# Esquematico.net
KiCad netlist of a schematic drawn in Altium Designer
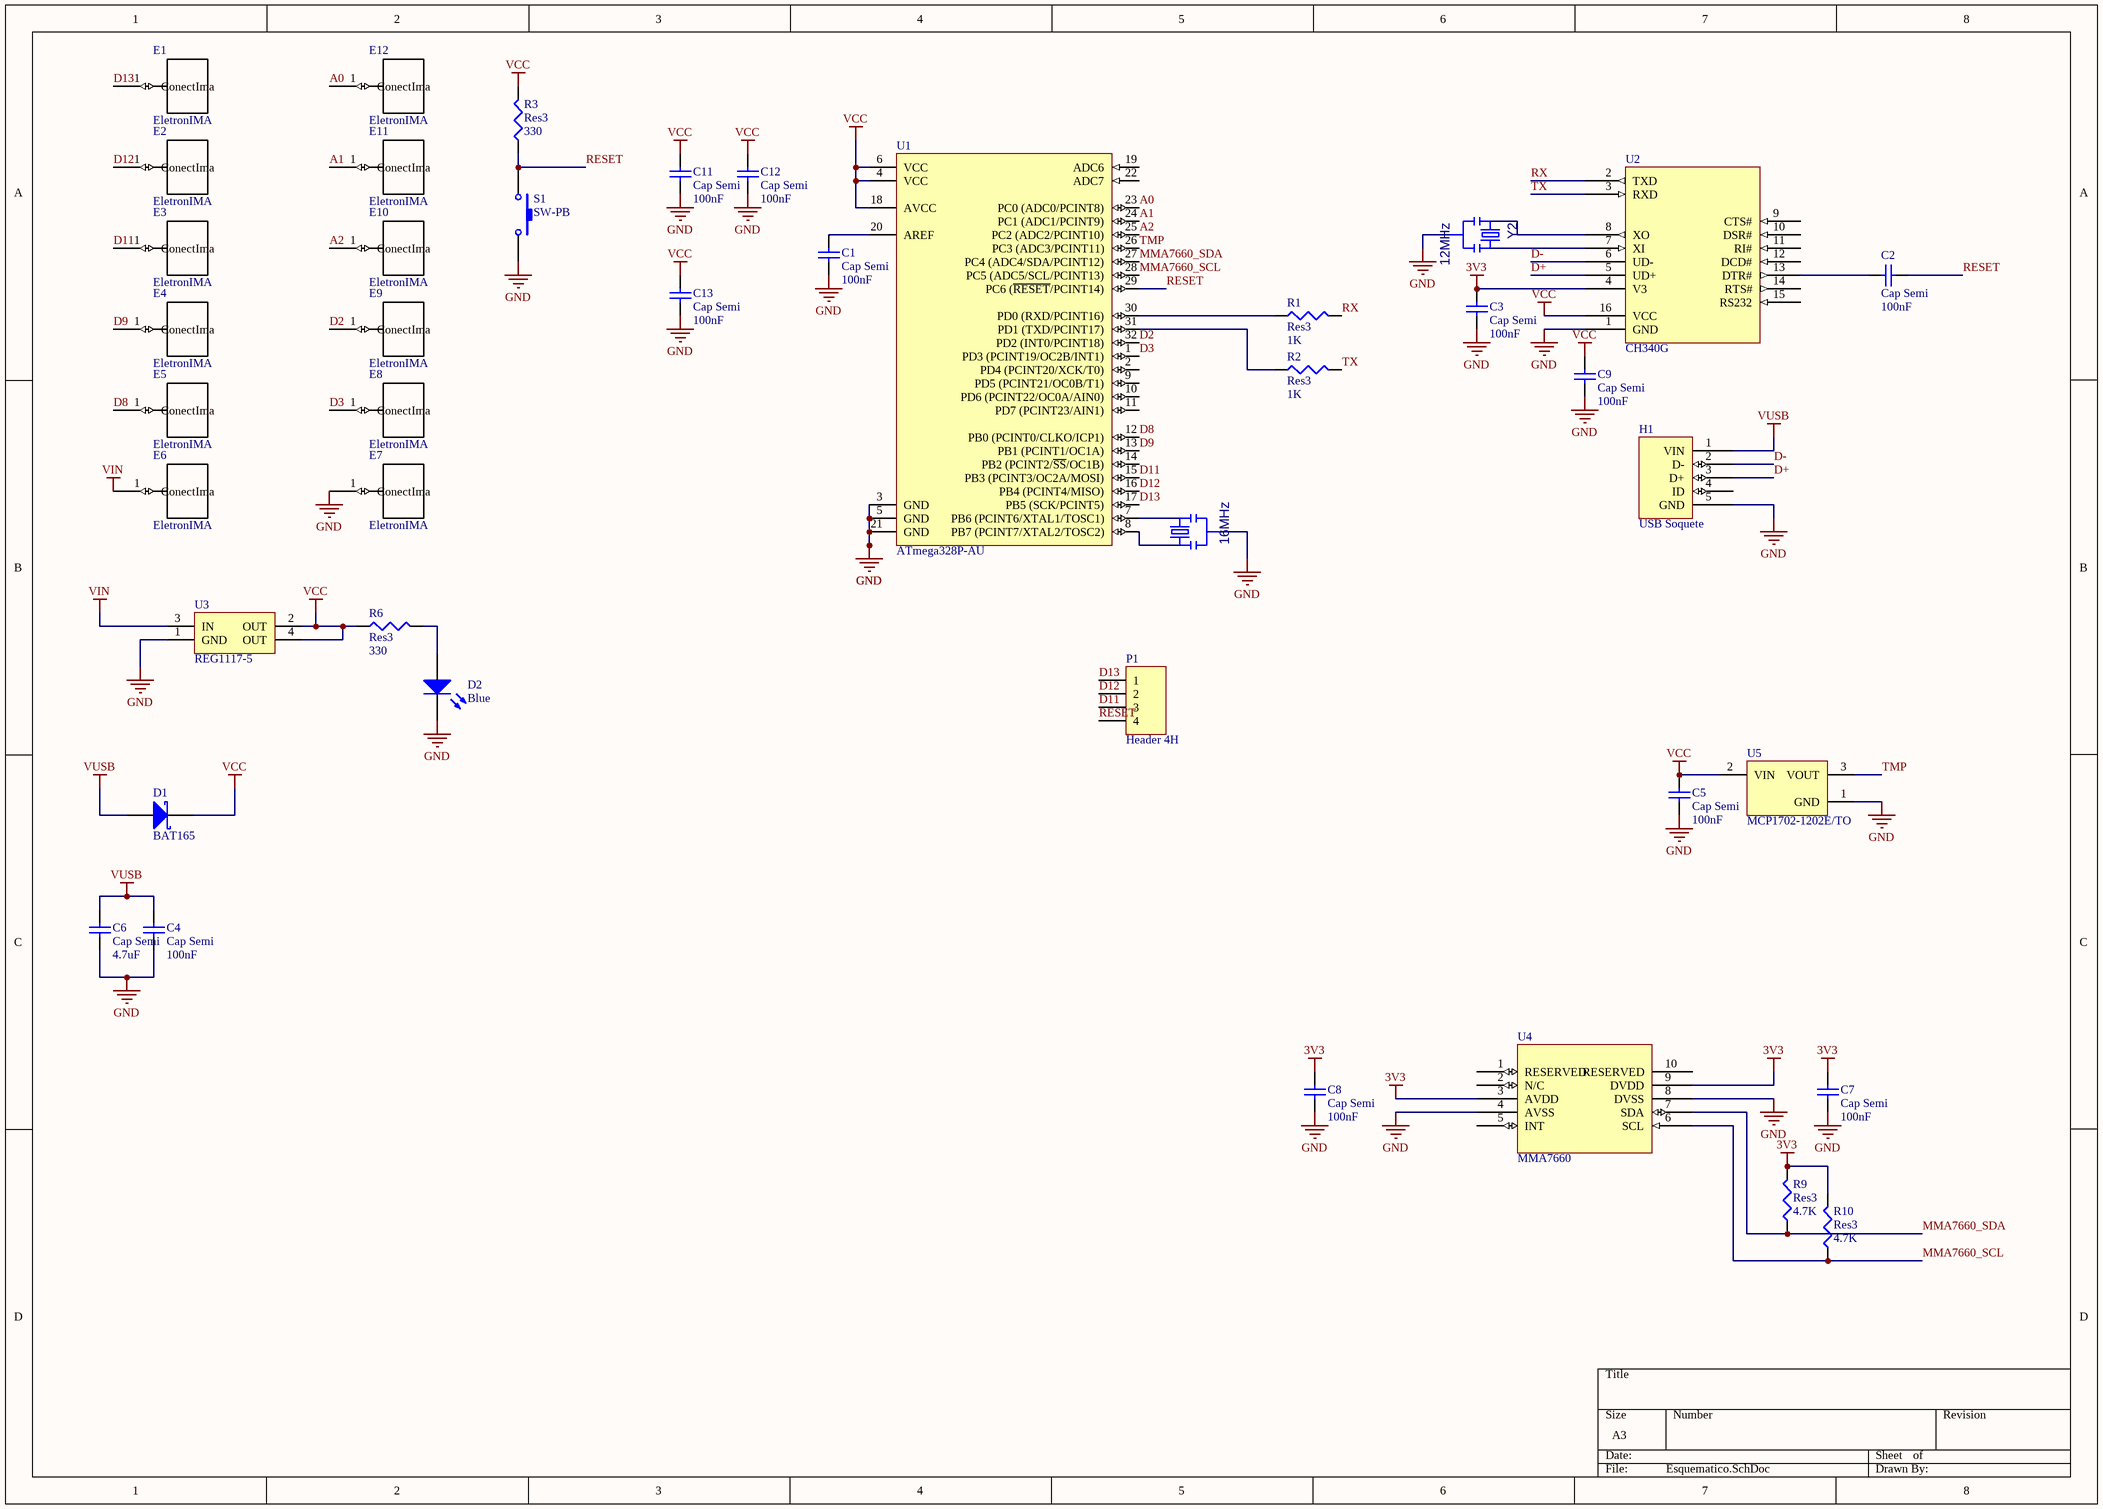
[diagram p0: Esquematico.SchDoc]

(export (version "E")
  (design (tool "Eeschema 10.0.6"))
  (components
    (comp (ref "C1")
      (value "Cap Semi")
      (footprint "0402")
      (description "Capacitor (Semiconductor SIM Model)")
      (fields (field (name "ALTIUM_VALUE") "100nF") (field (name "PUBLISHER") "Altium Limited"))
      (libsource (lib "Miscellaneous Devices") (part "Cap Semi"))
    )
    (comp (ref "C2")
      (value "Cap Semi")
      (footprint "0402")
      (description "Capacitor (Semiconductor SIM Model)")
      (fields (field (name "ALTIUM_VALUE") "100nF") (field (name "PUBLISHER") "Altium Limited"))
      (libsource (lib "Miscellaneous Devices") (part "Cap Semi"))
    )
    (comp (ref "C3")
      (value "Cap Semi")
      (footprint "0402")
      (description "Capacitor (Semiconductor SIM Model)")
      (fields (field (name "ALTIUM_VALUE") "100nF") (field (name "PUBLISHER") "Altium Limited"))
      (libsource (lib "Miscellaneous Devices") (part "Cap Semi"))
    )
    (comp (ref "C4")
      (value "Cap Semi")
      (footprint "0402")
      (description "Capacitor (Semiconductor SIM Model)")
      (fields (field (name "ALTIUM_VALUE") "100nF") (field (name "PUBLISHER") "Altium Limited"))
      (libsource (lib "Miscellaneous Devices") (part "Cap Semi"))
    )
    (comp (ref "C5")
      (value "Cap Semi")
      (footprint "0402")
      (description "Capacitor (Semiconductor SIM Model)")
      (fields (field (name "ALTIUM_VALUE") "100nF") (field (name "PUBLISHER") "Altium Limited"))
      (libsource (lib "Miscellaneous Devices") (part "Cap Semi"))
    )
    (comp (ref "C6")
      (value "Cap Semi")
      (footprint "0402")
      (description "Capacitor (Semiconductor SIM Model)")
      (fields (field (name "ALTIUM_VALUE") "4.7uF") (field (name "PUBLISHER") "Altium Limited"))
      (libsource (lib "Miscellaneous Devices") (part "Cap Semi"))
    )
    (comp (ref "C7")
      (value "Cap Semi")
      (footprint "0402")
      (description "Capacitor (Semiconductor SIM Model)")
      (fields (field (name "ALTIUM_VALUE") "100nF") (field (name "PUBLISHER") "Altium Limited"))
      (libsource (lib "Miscellaneous Devices") (part "Cap Semi"))
    )
    (comp (ref "C8")
      (value "Cap Semi")
      (footprint "0402")
      (description "Capacitor (Semiconductor SIM Model)")
      (fields (field (name "ALTIUM_VALUE") "100nF") (field (name "PUBLISHER") "Altium Limited"))
      (libsource (lib "Miscellaneous Devices") (part "Cap Semi"))
    )
    (comp (ref "C9")
      (value "Cap Semi")
      (footprint "0402")
      (description "Capacitor (Semiconductor SIM Model)")
      (fields (field (name "ALTIUM_VALUE") "100nF") (field (name "PUBLISHER") "Altium Limited"))
      (libsource (lib "Miscellaneous Devices") (part "Cap Semi"))
    )
    (comp (ref "C11")
      (value "Cap Semi")
      (footprint "0402")
      (description "Capacitor (Semiconductor SIM Model)")
      (fields (field (name "ALTIUM_VALUE") "100nF") (field (name "PUBLISHER") "Altium Limited"))
      (libsource (lib "Miscellaneous Devices") (part "Cap Semi"))
    )
    (comp (ref "C12")
      (value "Cap Semi")
      (footprint "0402")
      (description "Capacitor (Semiconductor SIM Model)")
      (fields (field (name "ALTIUM_VALUE") "100nF") (field (name "PUBLISHER") "Altium Limited"))
      (libsource (lib "Miscellaneous Devices") (part "Cap Semi"))
    )
    (comp (ref "C13")
      (value "Cap Semi")
      (footprint "0402")
      (description "Capacitor (Semiconductor SIM Model)")
      (fields (field (name "ALTIUM_VALUE") "100nF") (field (name "PUBLISHER") "Altium Limited"))
      (libsource (lib "Miscellaneous Devices") (part "Cap Semi"))
    )
    (comp (ref "D1")
      (value "BAT165")
      (footprint "SOD-323")
      (description "Silicon AF Schottky Rectifier Diode")
      (fields (field (name "PUBLISHER") "Altium Limited"))
      (libsource (lib "Infineon Discrete Diode") (part "BAT165"))
    )
    (comp (ref "D2")
      (value "Blue")
      (footprint "1.6X0.8X0.6")
      (description "Top Mount Low Profile Chip LED, Blue")
      (fields (field (name "PUBLISHER") "Altium Limited"))
      (libsource (lib "Agilent Optoelectronic LED") (part "HSMR-C191"))
    )
    (comp (ref "E1")
      (value "EletronIMA")
      (footprint "TermIma")
      (libsource (lib "Components") (part "EletronIMA"))
    )
    (comp (ref "E2")
      (value "EletronIMA")
      (footprint "TermIma")
      (libsource (lib "Components") (part "EletronIMA"))
    )
    (comp (ref "E3")
      (value "EletronIMA")
      (footprint "TermIma")
      (libsource (lib "Components") (part "EletronIMA"))
    )
    (comp (ref "E4")
      (value "EletronIMA")
      (footprint "TermIma")
      (libsource (lib "Components") (part "EletronIMA"))
    )
    (comp (ref "E5")
      (value "EletronIMA")
      (footprint "TermIma")
      (libsource (lib "Components") (part "EletronIMA"))
    )
    (comp (ref "E6")
      (value "EletronIMA")
      (footprint "TermIma")
      (libsource (lib "Components") (part "EletronIMA"))
    )
    (comp (ref "E7")
      (value "EletronIMA")
      (footprint "TermIma")
      (libsource (lib "Components") (part "EletronIMA"))
    )
    (comp (ref "E8")
      (value "EletronIMA")
      (footprint "TermIma")
      (libsource (lib "Components") (part "EletronIMA"))
    )
    (comp (ref "E9")
      (value "EletronIMA")
      (footprint "TermIma")
      (libsource (lib "Components") (part "EletronIMA"))
    )
    (comp (ref "E10")
      (value "EletronIMA")
      (footprint "TermIma")
      (libsource (lib "Components") (part "EletronIMA"))
    )
    (comp (ref "E11")
      (value "EletronIMA")
      (footprint "TermIma")
      (libsource (lib "Components") (part "EletronIMA"))
    )
    (comp (ref "E12")
      (value "EletronIMA")
      (footprint "TermIma")
      (libsource (lib "Components") (part "EletronIMA"))
    )
    (comp (ref "H1")
      (value "USB Soquete")
      (footprint "ZX62RD-AB-5P8")
      (libsource (lib "Components") (part "USB Soquete"))
    )
    (comp (ref "P1")
      (value "Header 4H")
      (footprint "HDR1X4H")
      (description "Header, 4-Pin, Right Angle")
      (fields (field (name "PUBLISHER") "Altium Limited"))
      (libsource (lib "Miscellaneous Connectors") (part "Header 4H"))
    )
    (comp (ref "R1")
      (value "Res3")
      (footprint "J1-0603")
      (description "Resistor")
      (fields (field (name "ALTIUM_VALUE") "1K") (field (name "PUBLISHER") "Altium Limited"))
      (libsource (lib "Miscellaneous Devices") (part "Res3"))
    )
    (comp (ref "R2")
      (value "Res3")
      (footprint "J1-0603")
      (description "Resistor")
      (fields (field (name "ALTIUM_VALUE") "1K") (field (name "PUBLISHER") "Altium Limited"))
      (libsource (lib "Miscellaneous Devices") (part "Res3"))
    )
    (comp (ref "R3")
      (value "Res3")
      (footprint "J1-0603")
      (description "Resistor")
      (fields (field (name "ALTIUM_VALUE") "330") (field (name "PUBLISHER") "Altium Limited"))
      (libsource (lib "Miscellaneous Devices") (part "Res3"))
    )
    (comp (ref "R6")
      (value "Res3")
      (footprint "J1-0603")
      (description "Resistor")
      (fields (field (name "ALTIUM_VALUE") "330") (field (name "PUBLISHER") "Altium Limited"))
      (libsource (lib "Miscellaneous Devices") (part "Res3"))
    )
    (comp (ref "R9")
      (value "Res3")
      (footprint "J1-0603")
      (description "Resistor")
      (fields (field (name "ALTIUM_VALUE") "4.7K") (field (name "PUBLISHER") "Altium Limited"))
      (libsource (lib "Miscellaneous Devices") (part "Res3"))
    )
    (comp (ref "R10")
      (value "Res3")
      (footprint "J1-0603")
      (description "Resistor")
      (fields (field (name "ALTIUM_VALUE") "4.7K") (field (name "PUBLISHER") "Altium Limited"))
      (libsource (lib "Miscellaneous Devices") (part "Res3"))
    )
    (comp (ref "S1")
      (value "SW-PB")
      (footprint "SPST")
      (description "Switch")
      (fields (field (name "PUBLISHER") "Altium Limited"))
      (libsource (lib "Miscellaneous Devices") (part "SW-PB"))
    )
    (comp (ref "U1")
      (value "ATmega328P-AU")
      (footprint "32A_N")
      (fields (field (name "PUBLISHER") "Altium Limited"))
      (libsource (lib "Atmel Microcontroller 8-Bit megaAVR") (part "ATmega328P-AU"))
    )
    (comp (ref "U2")
      (value "CH340G")
      (footprint "SSOP20")
      (description "USB to UART interface")
      (libsource (lib "Components") (part "CH340G"))
    )
    (comp (ref "U3")
      (value "REG1117-5")
      (footprint "SOT-223-DB3_M")
      (description "800mA and 1A Low Dropout Positive Regulator 2.85V, 3.3V, 5V, and Adjustable")
      (fields (field (name "PUBLISHER") "Altium Limited"))
      (libsource (lib "BB Power Mgt Voltage Regulator") (part "REG1117-5"))
    )
    (comp (ref "U4")
      (value "MMA7660")
      (footprint "Microchip Linear Devices:DFN-MF10")
      (description "Digital 3-Axis-Accelerometers Sensor;±16g")
      (libsource (lib "Components") (part "MMA7660"))
    )
    (comp (ref "U5")
      (value "MCP1702-1202E/TO")
      (footprint "TO-92-TO3")
      (description "250 mA Low Quiescent Current LDO Regulator, 3-Pin TO-92, Extended TemperatureBAG")
      (fields (field (name "PUBLISHER") "Altium Limited"))
      (libsource (lib "Microchip Power Mgt Line Regulator") (part "MCP1702-1202E/TO"))
    )
    (comp (ref "Y1")
      (value "16MHz")
      (footprint "X3-SMD-3.6X1.3X0.8MM")
      (description "Ceramic Resonator 16MHz ??0.5% (Tol) ??0.3% (Stability) 15pF 40Ohm 3-Pin CSMD T/R")
      (fields (field (name "MP") "CSTCE16M0V53-R0") (field (name "MF") "Murata"))
      (libsource (lib "SMD-RESONATOR-16MHZ-15PF-0.5_-40R_3P-3.2X1.3MM_") (part "SMD-RESONATOR-16MHZ-15PF-0.5%-40R(3P-3.2X1.3MM)"))
    )
    (comp (ref "Y2")
      (value "12MHz")
      (footprint "X3-SMD-3.6X1.3X0.8MM")
      (description "Ceramic Resonator 16MHz ??0.5% (Tol) ??0.3% (Stability) 15pF 40Ohm 3-Pin CSMD T/R")
      (fields (field (name "MP") "CSTCE16M0V53-R0") (field (name "MF") "Murata"))
      (libsource (lib "SMD-RESONATOR-16MHZ-15PF-0.5_-40R_3P-3.2X1.3MM_") (part "SMD-RESONATOR-16MHZ-15PF-0.5%-40R(3P-3.2X1.3MM)"))
    )
  )
  (nets
    (net (code "1") (name "/A0") (class "Default")
      (node (ref "E12") (pin "1") (pinfunction "ConectIma_1") (pintype "bidirectional"))
      (node (ref "U1") (pin "23") (pinfunction "PC0_(ADC0/PCINT8)_23") (pintype "bidirectional"))
    )
    (net (code "2") (name "/A1") (class "Default")
      (node (ref "E11") (pin "1") (pinfunction "ConectIma_1") (pintype "bidirectional"))
      (node (ref "U1") (pin "24") (pinfunction "PC1_(ADC1/PCINT9)_24") (pintype "bidirectional"))
    )
    (net (code "3") (name "/A2") (class "Default")
      (node (ref "E10") (pin "1") (pinfunction "ConectIma_1") (pintype "bidirectional"))
      (node (ref "U1") (pin "25") (pinfunction "PC2_(ADC2/PCINT10)_25") (pintype "bidirectional"))
    )
    (net (code "4") (name "/D+") (class "Default")
      (node (ref "H1") (pin "3") (pinfunction "D+_3") (pintype "bidirectional"))
      (node (ref "U2") (pin "5") (pinfunction "UD+_5") (pintype "open_collector"))
    )
    (net (code "5") (name "/D-") (class "Default")
      (node (ref "H1") (pin "2") (pinfunction "D-_2") (pintype "bidirectional"))
      (node (ref "U2") (pin "6") (pinfunction "UD-_6") (pintype "open_collector"))
    )
    (net (code "6") (name "/D2") (class "Default")
      (node (ref "E9") (pin "1") (pinfunction "ConectIma_1") (pintype "bidirectional"))
      (node (ref "U1") (pin "32") (pinfunction "PD2_(INT0/PCINT18)_32") (pintype "bidirectional"))
    )
    (net (code "7") (name "/D3") (class "Default")
      (node (ref "E8") (pin "1") (pinfunction "ConectIma_1") (pintype "bidirectional"))
      (node (ref "U1") (pin "1") (pinfunction "PD3_(PCINT19/OC2B/INT1)_1") (pintype "bidirectional"))
    )
    (net (code "8") (name "/D8") (class "Default")
      (node (ref "E5") (pin "1") (pinfunction "ConectIma_1") (pintype "bidirectional"))
      (node (ref "U1") (pin "12") (pinfunction "PB0_(PCINT0/CLKO/ICP1)_12") (pintype "bidirectional"))
    )
    (net (code "9") (name "/D9") (class "Default")
      (node (ref "E4") (pin "1") (pinfunction "ConectIma_1") (pintype "bidirectional"))
      (node (ref "U1") (pin "13") (pinfunction "PB1_(PCINT1/OC1A)_13") (pintype "bidirectional"))
    )
    (net (code "10") (name "/D11") (class "Default")
      (node (ref "E3") (pin "1") (pinfunction "ConectIma_1") (pintype "bidirectional"))
      (node (ref "P1") (pin "3") (pinfunction "3_3") (pintype "passive"))
      (node (ref "U1") (pin "15") (pinfunction "PB3_(PCINT3/OC2A/MOSI)_15") (pintype "bidirectional"))
    )
    (net (code "11") (name "/D12") (class "Default")
      (node (ref "E2") (pin "1") (pinfunction "ConectIma_1") (pintype "bidirectional"))
      (node (ref "P1") (pin "2") (pinfunction "2_2") (pintype "passive"))
      (node (ref "U1") (pin "16") (pinfunction "PB4_(PCINT4/MISO)_16") (pintype "bidirectional"))
    )
    (net (code "12") (name "/D13") (class "Default")
      (node (ref "E1") (pin "1") (pinfunction "ConectIma_1") (pintype "bidirectional"))
      (node (ref "P1") (pin "1") (pinfunction "1_1") (pintype "passive"))
      (node (ref "U1") (pin "17") (pinfunction "PB5_(SCK/PCINT5)_17") (pintype "bidirectional"))
    )
    (net (code "13") (name "/MMA7660_SCL") (class "Default")
      (node (ref "R10") (pin "1") (pinfunction "1_1") (pintype "passive"))
      (node (ref "U1") (pin "28") (pinfunction "PC5_(ADC5/SCL/PCINT13)_28") (pintype "bidirectional"))
      (node (ref "U4") (pin "6") (pinfunction "SCL_6") (pintype "input"))
    )
    (net (code "14") (name "/MMA7660_SDA") (class "Default")
      (node (ref "R9") (pin "1") (pinfunction "1_1") (pintype "passive"))
      (node (ref "U1") (pin "27") (pinfunction "PC4_(ADC4/SDA/PCINT12)_27") (pintype "bidirectional"))
      (node (ref "U4") (pin "7") (pinfunction "SDA_7") (pintype "bidirectional"))
    )
    (net (code "15") (name "/RESET") (class "Default")
      (node (ref "C2") (pin "2") (pinfunction "2_2") (pintype "passive"))
      (node (ref "P1") (pin "4") (pinfunction "4_4") (pintype "passive"))
      (node (ref "R3") (pin "1") (pinfunction "1_1") (pintype "passive"))
      (node (ref "S1") (pin "1") (pinfunction "1_1") (pintype "passive"))
      (node (ref "U1") (pin "29") (pinfunction "PC6_(~{RESET}/PCINT14)_29") (pintype "bidirectional"))
    )
    (net (code "16") (name "/RX") (class "Default")
      (node (ref "R1") (pin "2") (pinfunction "2_2") (pintype "passive"))
      (node (ref "U2") (pin "2") (pinfunction "TXD_2") (pintype "output"))
    )
    (net (code "17") (name "/TMP") (class "Default")
      (node (ref "U1") (pin "26") (pinfunction "PC3_(ADC3/PCINT11)_26") (pintype "bidirectional"))
      (node (ref "U5") (pin "3") (pinfunction "VOUT_3") (pintype "power_in"))
    )
    (net (code "18") (name "/TX") (class "Default")
      (node (ref "R2") (pin "2") (pinfunction "2_2") (pintype "passive"))
      (node (ref "U2") (pin "3") (pinfunction "RXD_3") (pintype "input"))
    )
    (net (code "19") (name "3V3") (class "Default")
      (node (ref "C3") (pin "2") (pinfunction "2_2") (pintype "passive"))
      (node (ref "C7") (pin "2") (pinfunction "2_2") (pintype "passive"))
      (node (ref "C8") (pin "1") (pinfunction "1_1") (pintype "passive"))
      (node (ref "R10") (pin "2") (pinfunction "2_2") (pintype "passive"))
      (node (ref "R9") (pin "2") (pinfunction "2_2") (pintype "passive"))
      (node (ref "U2") (pin "4") (pinfunction "V3_4") (pintype "power_in"))
      (node (ref "U4") (pin "3") (pinfunction "AVDD_3") (pintype "power_in"))
      (node (ref "U4") (pin "9") (pinfunction "DVDD_9") (pintype "power_in"))
    )
    (net (code "20") (name "GND") (class "Default")
      (node (ref "C1") (pin "1") (pinfunction "1_1") (pintype "passive"))
      (node (ref "C11") (pin "1") (pinfunction "1_1") (pintype "passive"))
      (node (ref "C12") (pin "1") (pinfunction "1_1") (pintype "passive"))
      (node (ref "C13") (pin "1") (pinfunction "1_1") (pintype "passive"))
      (node (ref "C3") (pin "1") (pinfunction "1_1") (pintype "passive"))
      (node (ref "C4") (pin "1") (pinfunction "1_1") (pintype "passive"))
      (node (ref "C5") (pin "1") (pinfunction "1_1") (pintype "passive"))
      (node (ref "C6") (pin "1") (pinfunction "1_1") (pintype "passive"))
      (node (ref "C7") (pin "1") (pinfunction "1_1") (pintype "passive"))
      (node (ref "C8") (pin "2") (pinfunction "2_2") (pintype "passive"))
      (node (ref "C9") (pin "1") (pinfunction "1_1") (pintype "passive"))
      (node (ref "D2") (pin "2") (pinfunction "K_2") (pintype "passive"))
      (node (ref "E7") (pin "1") (pinfunction "ConectIma_1") (pintype "bidirectional"))
      (node (ref "H1") (pin "5") (pinfunction "GND_5") (pintype "power_in"))
      (node (ref "S1") (pin "2") (pinfunction "2_2") (pintype "passive"))
      (node (ref "U1") (pin "21") (pinfunction "GND_21") (pintype "power_in"))
      (node (ref "U1") (pin "3") (pinfunction "GND_3") (pintype "power_in"))
      (node (ref "U1") (pin "5") (pinfunction "GND_5") (pintype "power_in"))
      (node (ref "U2") (pin "1") (pinfunction "GND_1") (pintype "power_in"))
      (node (ref "U3") (pin "1") (pinfunction "GND_1") (pintype "power_in"))
      (node (ref "U4") (pin "4") (pinfunction "AVSS_4") (pintype "power_in"))
      (node (ref "U4") (pin "8") (pinfunction "DVSS_8") (pintype "power_in"))
      (node (ref "U5") (pin "1") (pinfunction "GND_1") (pintype "power_in"))
      (node (ref "Y1") (pin "2") (pinfunction "2_2") (pintype "passive"))
      (node (ref "Y2") (pin "2") (pinfunction "2_2") (pintype "passive"))
    )
    (net (code "21") (name "Net-(D2-A)") (class "Default")
      (node (ref "D2") (pin "1") (pinfunction "A_1") (pintype "passive"))
      (node (ref "R6") (pin "2") (pinfunction "2_2") (pintype "passive"))
    )
    (net (code "22") (name "Net-(U1-AREF)") (class "Default")
      (node (ref "C1") (pin "2") (pinfunction "2_2") (pintype "passive"))
      (node (ref "U1") (pin "20") (pinfunction "AREF_20") (pintype "passive"))
    )
    (net (code "23") (name "Net-(U1-PB6_(PCINT6{slash}XTAL1{slash}TOSC1))") (class "Default")
      (node (ref "U1") (pin "7") (pinfunction "PB6_(PCINT6/XTAL1/TOSC1)_7") (pintype "bidirectional"))
      (node (ref "Y1") (pin "3") (pinfunction "3_3") (pintype "passive"))
    )
    (net (code "24") (name "Net-(U1-PB7_(PCINT7{slash}XTAL2{slash}TOSC2))") (class "Default")
      (node (ref "U1") (pin "8") (pinfunction "PB7_(PCINT7/XTAL2/TOSC2)_8") (pintype "bidirectional"))
      (node (ref "Y1") (pin "1") (pinfunction "1_1") (pintype "passive"))
    )
    (net (code "25") (name "Net-(U1-PD0_(RXD{slash}PCINT16))") (class "Default")
      (node (ref "R1") (pin "1") (pinfunction "1_1") (pintype "passive"))
      (node (ref "U1") (pin "30") (pinfunction "PD0_(RXD/PCINT16)_30") (pintype "bidirectional"))
    )
    (net (code "26") (name "Net-(U1-PD1_(TXD{slash}PCINT17))") (class "Default")
      (node (ref "R2") (pin "1") (pinfunction "1_1") (pintype "passive"))
      (node (ref "U1") (pin "31") (pinfunction "PD1_(TXD/PCINT17)_31") (pintype "bidirectional"))
    )
    (net (code "27") (name "Net-(U2-DTR#)") (class "Default")
      (node (ref "C2") (pin "1") (pinfunction "1_1") (pintype "passive"))
      (node (ref "U2") (pin "13") (pinfunction "DTR#_13") (pintype "output"))
    )
    (net (code "28") (name "Net-(U2-XI)") (class "Default")
      (node (ref "U2") (pin "7") (pinfunction "XI_7") (pintype "input"))
      (node (ref "Y2") (pin "3") (pinfunction "3_3") (pintype "passive"))
    )
    (net (code "29") (name "Net-(U2-XO)") (class "Default")
      (node (ref "U2") (pin "8") (pinfunction "XO_8") (pintype "output"))
      (node (ref "Y2") (pin "1") (pinfunction "1_1") (pintype "passive"))
    )
    (net (code "30") (name "VCC") (class "Default")
      (node (ref "C11") (pin "2") (pinfunction "2_2") (pintype "passive"))
      (node (ref "C12") (pin "2") (pinfunction "2_2") (pintype "passive"))
      (node (ref "C13") (pin "2") (pinfunction "2_2") (pintype "passive"))
      (node (ref "C5") (pin "2") (pinfunction "2_2") (pintype "passive"))
      (node (ref "C9") (pin "2") (pinfunction "2_2") (pintype "passive"))
      (node (ref "D1") (pin "1") (pinfunction "K_1") (pintype "passive"))
      (node (ref "R3") (pin "2") (pinfunction "2_2") (pintype "passive"))
      (node (ref "R6") (pin "1") (pinfunction "1_1") (pintype "passive"))
      (node (ref "U1") (pin "18") (pinfunction "AVCC_18") (pintype "power_in"))
      (node (ref "U1") (pin "4") (pinfunction "VCC_4") (pintype "power_in"))
      (node (ref "U1") (pin "6") (pinfunction "VCC_6") (pintype "power_in"))
      (node (ref "U2") (pin "16") (pinfunction "VCC_16") (pintype "power_in"))
      (node (ref "U3") (pin "2") (pinfunction "OUT_2") (pintype "power_in"))
      (node (ref "U3") (pin "4") (pinfunction "OUT_4") (pintype "power_in"))
      (node (ref "U5") (pin "2") (pinfunction "VIN_2") (pintype "power_in"))
    )
    (net (code "31") (name "VIN") (class "Default")
      (node (ref "E6") (pin "1") (pinfunction "ConectIma_1") (pintype "bidirectional"))
      (node (ref "U3") (pin "3") (pinfunction "IN_3") (pintype "power_in"))
    )
    (net (code "32") (name "VUSB") (class "Default")
      (node (ref "C4") (pin "2") (pinfunction "2_2") (pintype "passive"))
      (node (ref "C6") (pin "2") (pinfunction "2_2") (pintype "passive"))
      (node (ref "D1") (pin "2") (pinfunction "A_2") (pintype "passive"))
      (node (ref "H1") (pin "1") (pinfunction "VIN_1") (pintype "power_in"))
    )
    (net (code "33") (name "unconnected-(H1-ID-Pad4)") (class "Default")
      (node (ref "H1") (pin "4") (pinfunction "ID_4") (pintype "bidirectional"))
    )
    (net (code "34") (name "unconnected-(U1-ADC6-Pad19)") (class "Default")
      (node (ref "U1") (pin "19") (pinfunction "ADC6_19") (pintype "input"))
    )
    (net (code "35") (name "unconnected-(U1-ADC7-Pad22)") (class "Default")
      (node (ref "U1") (pin "22") (pinfunction "ADC7_22") (pintype "input"))
    )
    (net (code "36") (name "unconnected-(U1-PB2_(PCINT2{slash}~{SS}{slash}OC1B)-Pad14)") (class "Default")
      (node (ref "U1") (pin "14") (pinfunction "PB2_(PCINT2/~{SS}/OC1B)_14") (pintype "bidirectional"))
    )
    (net (code "37") (name "unconnected-(U1-PD4_(PCINT20{slash}XCK{slash}T0)-Pad2)") (class "Default")
      (node (ref "U1") (pin "2") (pinfunction "PD4_(PCINT20/XCK/T0)_2") (pintype "bidirectional"))
    )
    (net (code "38") (name "unconnected-(U1-PD5_(PCINT21{slash}OC0B{slash}T1)-Pad9)") (class "Default")
      (node (ref "U1") (pin "9") (pinfunction "PD5_(PCINT21/OC0B/T1)_9") (pintype "bidirectional"))
    )
    (net (code "39") (name "unconnected-(U1-PD6_(PCINT22{slash}OC0A{slash}AIN0)-Pad10)") (class "Default")
      (node (ref "U1") (pin "10") (pinfunction "PD6_(PCINT22/OC0A/AIN0)_10") (pintype "bidirectional"))
    )
    (net (code "40") (name "unconnected-(U1-PD7_(PCINT23{slash}AIN1)-Pad11)") (class "Default")
      (node (ref "U1") (pin "11") (pinfunction "PD7_(PCINT23/AIN1)_11") (pintype "bidirectional"))
    )
    (net (code "41") (name "unconnected-(U2-CTS#-Pad9)") (class "Default")
      (node (ref "U2") (pin "9") (pinfunction "CTS#_9") (pintype "input"))
    )
    (net (code "42") (name "unconnected-(U2-DCD#-Pad12)") (class "Default")
      (node (ref "U2") (pin "12") (pinfunction "DCD#_12") (pintype "input"))
    )
    (net (code "43") (name "unconnected-(U2-DSR#-Pad10)") (class "Default")
      (node (ref "U2") (pin "10") (pinfunction "DSR#_10") (pintype "input"))
    )
    (net (code "44") (name "unconnected-(U2-RI#-Pad11)") (class "Default")
      (node (ref "U2") (pin "11") (pinfunction "RI#_11") (pintype "input"))
    )
    (net (code "45") (name "unconnected-(U2-RS232-Pad15)") (class "Default")
      (node (ref "U2") (pin "15") (pinfunction "RS232_15") (pintype "input"))
    )
    (net (code "46") (name "unconnected-(U2-RTS#-Pad14)") (class "Default")
      (node (ref "U2") (pin "14") (pinfunction "RTS#_14") (pintype "output"))
    )
    (net (code "47") (name "unconnected-(U4-INT-Pad5)") (class "Default")
      (node (ref "U4") (pin "5") (pinfunction "INT_5") (pintype "bidirectional"))
    )
    (net (code "48") (name "unconnected-(U4-N{slash}C-Pad2)") (class "Default")
      (node (ref "U4") (pin "2") (pinfunction "N/C_2") (pintype "bidirectional"))
    )
    (net (code "49") (name "unconnected-(U4-RESERVED-Pad1)") (class "Default")
      (node (ref "U4") (pin "1") (pinfunction "RESERVED_1") (pintype "bidirectional"))
    )
    (net (code "50") (name "unconnected-(U4-RESERVED-Pad10)") (class "Default")
      (node (ref "U4") (pin "10") (pinfunction "RESERVED_10") (pintype "power_in"))
    )
  )
)
